# rf_board.net
KiCad netlist of a schematic drawn in EAGLE
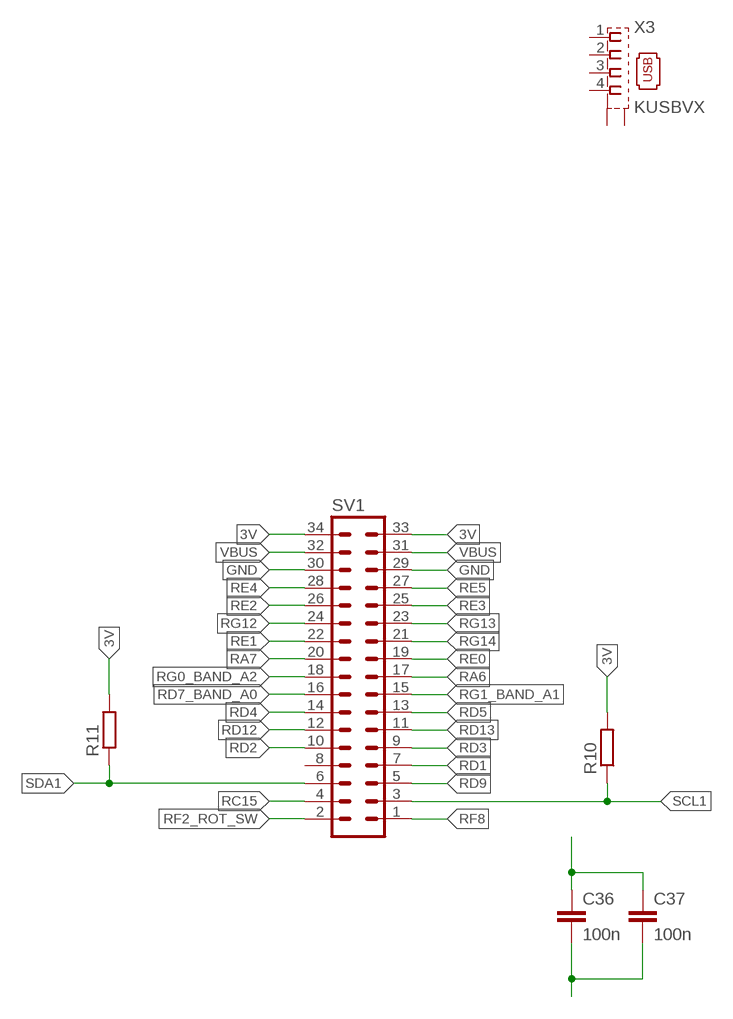
[diagram p0: schematic, sheet 1, part 1 of 2]
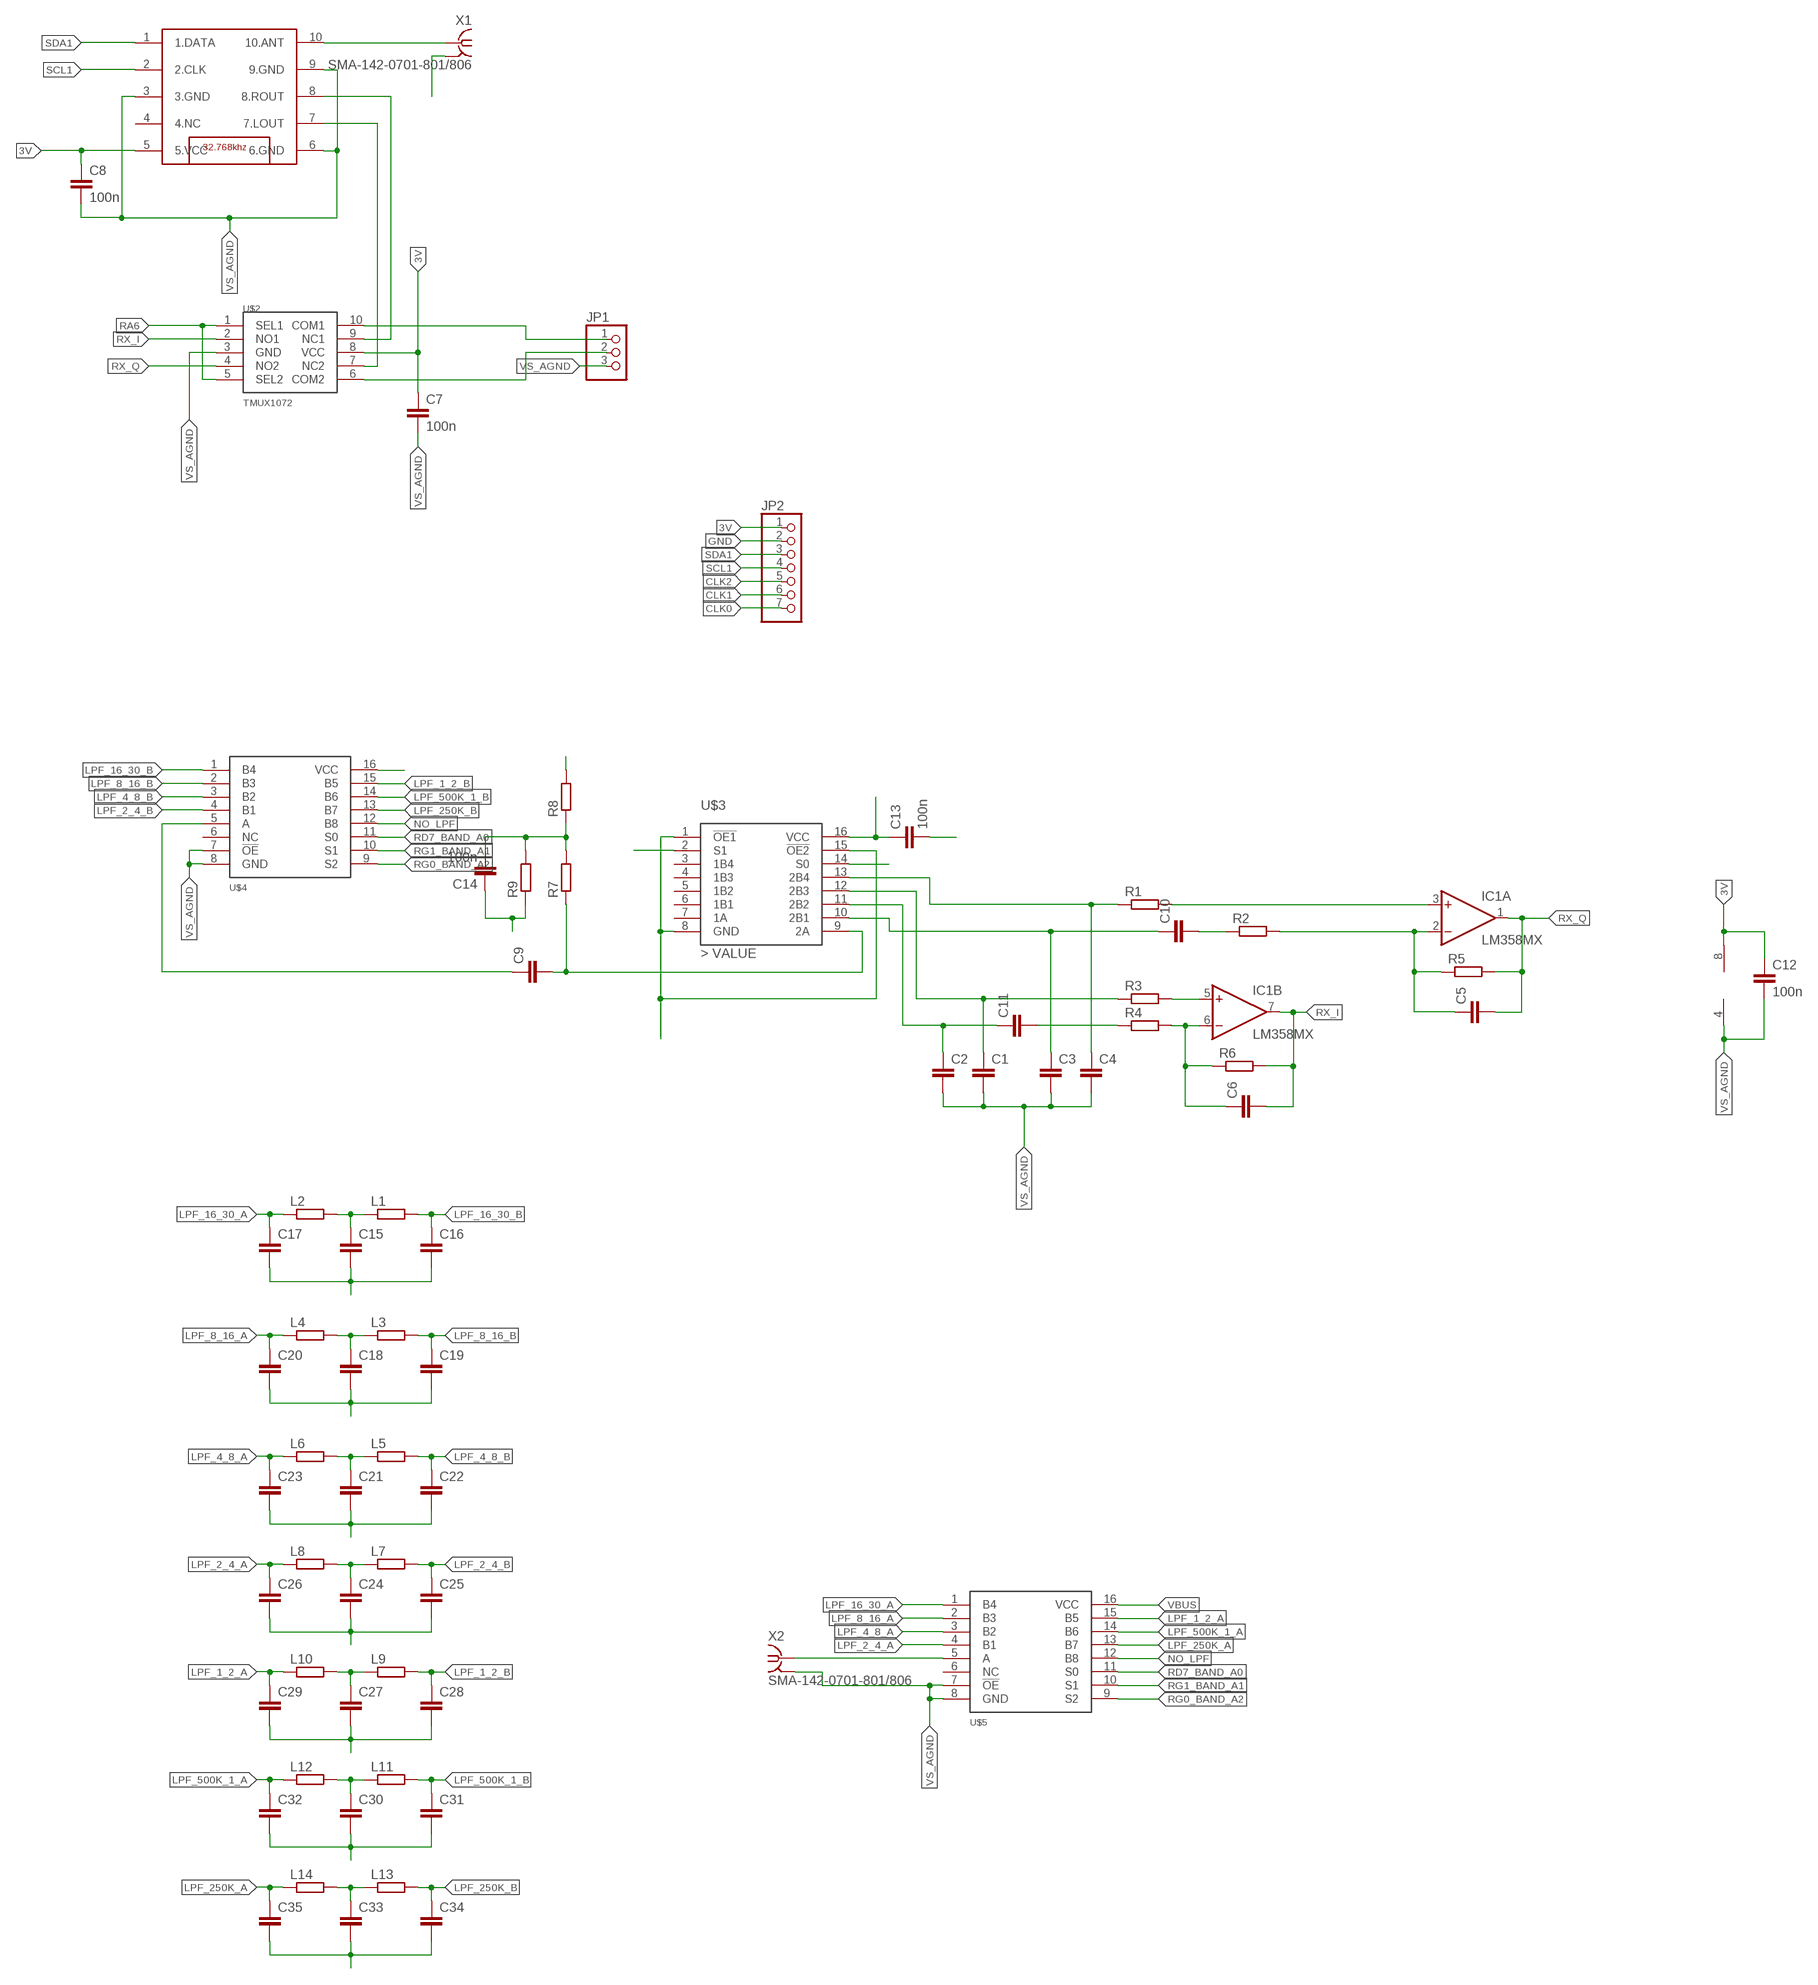
[diagram p1: schematic, sheet 1, part 2 of 2]

(export (version "E")
  (design (tool "Eeschema 10.0.6"))
  (components
    (comp (ref "C1")
      (value "C-EUC0603")
      (footprint "eagle-import:C0603")
      (libsource (lib "eagle-import") (part "C-EUC0603"))
    )
    (comp (ref "C2")
      (value "C-EUC0603")
      (footprint "eagle-import:C0603")
      (libsource (lib "eagle-import") (part "C-EUC0603"))
    )
    (comp (ref "C3")
      (value "C-EUC0603")
      (footprint "eagle-import:C0603")
      (libsource (lib "eagle-import") (part "C-EUC0603"))
    )
    (comp (ref "C4")
      (value "C-EUC0603")
      (footprint "eagle-import:C0603")
      (libsource (lib "eagle-import") (part "C-EUC0603"))
    )
    (comp (ref "C5")
      (value "C-EUC0603")
      (footprint "eagle-import:C0603")
      (libsource (lib "eagle-import") (part "C-EUC0603"))
    )
    (comp (ref "C6")
      (value "C-EUC0603")
      (footprint "eagle-import:C0603")
      (libsource (lib "eagle-import") (part "C-EUC0603"))
    )
    (comp (ref "C7")
      (value "100n")
      (footprint "eagle-import:C1206")
      (libsource (lib "eagle-import") (part "C-EUC1206"))
    )
    (comp (ref "C8")
      (value "100n")
      (footprint "eagle-import:C0603")
      (libsource (lib "eagle-import") (part "C-EUC0603"))
    )
    (comp (ref "C9")
      (value "C-EUC0603")
      (footprint "eagle-import:C0603")
      (libsource (lib "eagle-import") (part "C-EUC0603"))
    )
    (comp (ref "C10")
      (value "C-EUC0603")
      (footprint "eagle-import:C0603")
      (libsource (lib "eagle-import") (part "C-EUC0603"))
    )
    (comp (ref "C11")
      (value "C-EUC0603")
      (footprint "eagle-import:C0603")
      (libsource (lib "eagle-import") (part "C-EUC0603"))
    )
    (comp (ref "C12")
      (value "100n")
      (footprint "eagle-import:C0603")
      (libsource (lib "eagle-import") (part "C-EUC0603"))
    )
    (comp (ref "C13")
      (value "100n")
      (footprint "eagle-import:C0603")
      (libsource (lib "eagle-import") (part "C-EUC0603"))
    )
    (comp (ref "C14")
      (value "100n")
      (footprint "eagle-import:C0603")
      (libsource (lib "eagle-import") (part "C-EUC0603"))
    )
    (comp (ref "C15")
      (value "C-EUC0805")
      (footprint "eagle-import:C0805")
      (libsource (lib "eagle-import") (part "C-EUC0805"))
    )
    (comp (ref "C16")
      (value "C-EUC0805")
      (footprint "eagle-import:C0805")
      (libsource (lib "eagle-import") (part "C-EUC0805"))
    )
    (comp (ref "C17")
      (value "C-EUC0805")
      (footprint "eagle-import:C0805")
      (libsource (lib "eagle-import") (part "C-EUC0805"))
    )
    (comp (ref "C18")
      (value "C-EUC0805")
      (footprint "eagle-import:C0805")
      (libsource (lib "eagle-import") (part "C-EUC0805"))
    )
    (comp (ref "C19")
      (value "C-EUC0805")
      (footprint "eagle-import:C0805")
      (libsource (lib "eagle-import") (part "C-EUC0805"))
    )
    (comp (ref "C20")
      (value "C-EUC0805")
      (footprint "eagle-import:C0805")
      (libsource (lib "eagle-import") (part "C-EUC0805"))
    )
    (comp (ref "C21")
      (value "C-EUC0805")
      (footprint "eagle-import:C0805")
      (libsource (lib "eagle-import") (part "C-EUC0805"))
    )
    (comp (ref "C22")
      (value "C-EUC0805")
      (footprint "eagle-import:C0805")
      (libsource (lib "eagle-import") (part "C-EUC0805"))
    )
    (comp (ref "C23")
      (value "C-EUC0805")
      (footprint "eagle-import:C0805")
      (libsource (lib "eagle-import") (part "C-EUC0805"))
    )
    (comp (ref "C24")
      (value "C-EUC0805")
      (footprint "eagle-import:C0805")
      (libsource (lib "eagle-import") (part "C-EUC0805"))
    )
    (comp (ref "C25")
      (value "C-EUC0805")
      (footprint "eagle-import:C0805")
      (libsource (lib "eagle-import") (part "C-EUC0805"))
    )
    (comp (ref "C26")
      (value "C-EUC0805")
      (footprint "eagle-import:C0805")
      (libsource (lib "eagle-import") (part "C-EUC0805"))
    )
    (comp (ref "C27")
      (value "C-EUC0805")
      (footprint "eagle-import:C0805")
      (libsource (lib "eagle-import") (part "C-EUC0805"))
    )
    (comp (ref "C28")
      (value "C-EUC0805")
      (footprint "eagle-import:C0805")
      (libsource (lib "eagle-import") (part "C-EUC0805"))
    )
    (comp (ref "C29")
      (value "C-EUC0805")
      (footprint "eagle-import:C0805")
      (libsource (lib "eagle-import") (part "C-EUC0805"))
    )
    (comp (ref "C30")
      (value "C-EUC0805")
      (footprint "eagle-import:C0805")
      (libsource (lib "eagle-import") (part "C-EUC0805"))
    )
    (comp (ref "C31")
      (value "C-EUC0805")
      (footprint "eagle-import:C0805")
      (libsource (lib "eagle-import") (part "C-EUC0805"))
    )
    (comp (ref "C32")
      (value "C-EUC0805")
      (footprint "eagle-import:C0805")
      (libsource (lib "eagle-import") (part "C-EUC0805"))
    )
    (comp (ref "C33")
      (value "C-EUC0805")
      (footprint "eagle-import:C0805")
      (libsource (lib "eagle-import") (part "C-EUC0805"))
    )
    (comp (ref "C34")
      (value "C-EUC0805")
      (footprint "eagle-import:C0805")
      (libsource (lib "eagle-import") (part "C-EUC0805"))
    )
    (comp (ref "C35")
      (value "C-EUC0805")
      (footprint "eagle-import:C0805")
      (libsource (lib "eagle-import") (part "C-EUC0805"))
    )
    (comp (ref "C36")
      (value "100n")
      (footprint "eagle-import:C0603")
      (libsource (lib "eagle-import") (part "C-EUC0603"))
    )
    (comp (ref "C37")
      (value "100n")
      (footprint "eagle-import:C0603")
      (libsource (lib "eagle-import") (part "C-EUC0603"))
    )
    (comp (ref "IC1")
      (value "LM358MX")
      (footprint "eagle-import:SO08")
      (libsource (lib "eagle-import") (part "LM358MX"))
    )
    (comp (ref "JP1")
      (value "PINHD-1X3")
      (footprint "eagle-import:1X03")
      (libsource (lib "eagle-import") (part "PINHD-1X3"))
    )
    (comp (ref "JP2")
      (value "PINHD-1X7")
      (footprint "eagle-import:1X07")
      (libsource (lib "eagle-import") (part "PINHD-1X7"))
    )
    (comp (ref "L1")
      (value "R-EU_R0805")
      (footprint "eagle-import:R0805")
      (libsource (lib "eagle-import") (part "R-EU_R0805"))
    )
    (comp (ref "L2")
      (value "R-EU_R0805")
      (footprint "eagle-import:R0805")
      (libsource (lib "eagle-import") (part "R-EU_R0805"))
    )
    (comp (ref "L3")
      (value "R-EU_R0805")
      (footprint "eagle-import:R0805")
      (libsource (lib "eagle-import") (part "R-EU_R0805"))
    )
    (comp (ref "L4")
      (value "R-EU_R0805")
      (footprint "eagle-import:R0805")
      (libsource (lib "eagle-import") (part "R-EU_R0805"))
    )
    (comp (ref "L5")
      (value "R-EU_R0805")
      (footprint "eagle-import:R0805")
      (libsource (lib "eagle-import") (part "R-EU_R0805"))
    )
    (comp (ref "L6")
      (value "R-EU_R0805")
      (footprint "eagle-import:R0805")
      (libsource (lib "eagle-import") (part "R-EU_R0805"))
    )
    (comp (ref "L7")
      (value "R-EU_R0805")
      (footprint "eagle-import:R0805")
      (libsource (lib "eagle-import") (part "R-EU_R0805"))
    )
    (comp (ref "L8")
      (value "R-EU_R0805")
      (footprint "eagle-import:R0805")
      (libsource (lib "eagle-import") (part "R-EU_R0805"))
    )
    (comp (ref "L9")
      (value "R-EU_R0805")
      (footprint "eagle-import:R0805")
      (libsource (lib "eagle-import") (part "R-EU_R0805"))
    )
    (comp (ref "L10")
      (value "R-EU_R0805")
      (footprint "eagle-import:R0805")
      (libsource (lib "eagle-import") (part "R-EU_R0805"))
    )
    (comp (ref "L11")
      (value "R-EU_R0805")
      (footprint "eagle-import:R0805")
      (libsource (lib "eagle-import") (part "R-EU_R0805"))
    )
    (comp (ref "L12")
      (value "R-EU_R0805")
      (footprint "eagle-import:R0805")
      (libsource (lib "eagle-import") (part "R-EU_R0805"))
    )
    (comp (ref "L13")
      (value "R-EU_R0805")
      (footprint "eagle-import:R0805")
      (libsource (lib "eagle-import") (part "R-EU_R0805"))
    )
    (comp (ref "L14")
      (value "R-EU_R0805")
      (footprint "eagle-import:R0805")
      (libsource (lib "eagle-import") (part "R-EU_R0805"))
    )
    (comp (ref "R1")
      (value "R-EU_R0603")
      (footprint "eagle-import:R0603")
      (libsource (lib "eagle-import") (part "R-EU_R0603"))
    )
    (comp (ref "R2")
      (value "R-EU_R0603")
      (footprint "eagle-import:R0603")
      (libsource (lib "eagle-import") (part "R-EU_R0603"))
    )
    (comp (ref "R3")
      (value "R-EU_R0603")
      (footprint "eagle-import:R0603")
      (libsource (lib "eagle-import") (part "R-EU_R0603"))
    )
    (comp (ref "R4")
      (value "R-EU_R0603")
      (footprint "eagle-import:R0603")
      (libsource (lib "eagle-import") (part "R-EU_R0603"))
    )
    (comp (ref "R5")
      (value "R-EU_R0603")
      (footprint "eagle-import:R0603")
      (libsource (lib "eagle-import") (part "R-EU_R0603"))
    )
    (comp (ref "R6")
      (value "R-EU_R0603")
      (footprint "eagle-import:R0603")
      (libsource (lib "eagle-import") (part "R-EU_R0603"))
    )
    (comp (ref "R7")
      (value "R-EU_0204/5")
      (footprint "eagle-import:0204_5")
      (libsource (lib "eagle-import") (part "R-EU_0204/5"))
    )
    (comp (ref "R8")
      (value "R-EU_R0603")
      (footprint "eagle-import:R0603")
      (libsource (lib "eagle-import") (part "R-EU_R0603"))
    )
    (comp (ref "R9")
      (value "R-EU_R0603")
      (footprint "eagle-import:R0603")
      (libsource (lib "eagle-import") (part "R-EU_R0603"))
    )
    (comp (ref "R10")
      (value "R-EU_0204/7")
      (footprint "eagle-import:0204_7")
      (libsource (lib "eagle-import") (part "R-EU_0204/7"))
    )
    (comp (ref "R11")
      (value "R-EU_0204/5")
      (footprint "eagle-import:0204_5")
      (libsource (lib "eagle-import") (part "R-EU_0204/5"))
    )
    (comp (ref "SV1")
      (value "ML34L")
      (footprint "eagle-import:ML34L")
      (libsource (lib "eagle-import") (part "ML34L"))
    )
    (comp (ref "U$1")
      (value "TEA5767")
      (footprint "eagle-import:TJ-102BC")
      (libsource (lib "eagle-import") (part "TEA5767"))
    )
    (comp (ref "U$2")
      (value "TMUX1072")
      (footprint "eagle-import:TSSOP8")
      (libsource (lib "eagle-import") (part "TMUX1072"))
    )
    (comp (ref "U$3")
      (value "FST3253SO16")
      (footprint "eagle-import:SO16")
      (libsource (lib "eagle-import") (part "FST3253SO16"))
    )
    (comp (ref "U$4")
      (value "SN74CBT3251")
      (footprint "eagle-import:TSSOP16")
      (libsource (lib "eagle-import") (part "SN74CBT3251"))
    )
    (comp (ref "U$5")
      (value "SN74CBT3251")
      (footprint "eagle-import:TSSOP16")
      (libsource (lib "eagle-import") (part "SN74CBT3251"))
    )
    (comp (ref "X1")
      (value "SMA-142-0701-801/806")
      (footprint "eagle-import:J502-ND-142-0701-801_806")
      (fields (field (name "MF") "JOHNSON COMPONENTS") (field (name "MPN") "142-0701-801"))
      (libsource (lib "eagle-import") (part "SMA-142-0701-801/806"))
    )
    (comp (ref "X2")
      (value "SMA-142-0701-801/806")
      (footprint "eagle-import:J502-ND-142-0701-801_806")
      (fields (field (name "MF") "JOHNSON COMPONENTS") (field (name "MPN") "142-0701-801"))
      (libsource (lib "eagle-import") (part "SMA-142-0701-801/806"))
    )
    (comp (ref "X3")
      (value "KUSBVX")
      (footprint "eagle-import:KUSBVX")
      (libsource (lib "eagle-import") (part "KUSBVX"))
    )
  )
  (nets
    (net (code "1") (name "3V") (class "Default")
      (node (ref "C12") (pin "1") (pinfunction "1_1") (pintype "passive"))
      (node (ref "C13") (pin "1") (pinfunction "1_1") (pintype "passive"))
      (node (ref "C7") (pin "1") (pinfunction "1_1") (pintype "passive"))
      (node (ref "C8") (pin "1") (pinfunction "1_1") (pintype "passive"))
      (node (ref "IC1") (pin "8") (pinfunction "V+_8") (pintype "power_in"))
      (node (ref "JP2") (pin "1") (pinfunction "1_1") (pintype "passive"))
      (node (ref "R10") (pin "2") (pinfunction "2_2") (pintype "passive"))
      (node (ref "R11") (pin "2") (pinfunction "2_2") (pintype "passive"))
      (node (ref "R8") (pin "2") (pinfunction "2_2") (pintype "passive"))
      (node (ref "SV1") (pin "33") (pinfunction "33_33") (pintype "passive"))
      (node (ref "SV1") (pin "34") (pinfunction "34_34") (pintype "passive"))
      (node (ref "U$1") (pin "5") (pinfunction "5.VCC_5") (pintype "bidirectional"))
      (node (ref "U$2") (pin "8") (pinfunction "VCC_8") (pintype "bidirectional"))
      (node (ref "U$3") (pin "16") (pinfunction "VCC_16") (pintype "bidirectional"))
    )
    (net (code "2") (name "CLK0") (class "Default")
      (node (ref "JP2") (pin "7") (pinfunction "7_7") (pintype "passive"))
      (node (ref "U$3") (pin "14") (pinfunction "S0_14") (pintype "bidirectional"))
    )
    (net (code "3") (name "CLK1") (class "Default")
      (node (ref "JP2") (pin "6") (pinfunction "6_6") (pintype "passive"))
      (node (ref "U$3") (pin "2") (pinfunction "S1_2") (pintype "bidirectional"))
    )
    (net (code "4") (name "CLK2") (class "Default")
      (node (ref "JP2") (pin "5") (pinfunction "5_5") (pintype "passive"))
    )
    (net (code "5") (name "GND") (class "Default")
      (node (ref "JP2") (pin "2") (pinfunction "2_2") (pintype "passive"))
      (node (ref "SV1") (pin "29") (pinfunction "29_29") (pintype "passive"))
      (node (ref "SV1") (pin "30") (pinfunction "30_30") (pintype "passive"))
    )
    (net (code "6") (name "LPF_1_2_A") (class "Default")
      (node (ref "C29") (pin "1") (pinfunction "1_1") (pintype "passive"))
      (node (ref "L10") (pin "1") (pinfunction "1_1") (pintype "passive"))
      (node (ref "U$5") (pin "15") (pinfunction "B5_15") (pintype "bidirectional"))
    )
    (net (code "7") (name "LPF_1_2_B") (class "Default")
      (node (ref "C28") (pin "1") (pinfunction "1_1") (pintype "passive"))
      (node (ref "L9") (pin "2") (pinfunction "2_2") (pintype "passive"))
      (node (ref "U$4") (pin "15") (pinfunction "B5_15") (pintype "bidirectional"))
    )
    (net (code "8") (name "LPF_2_4_A") (class "Default")
      (node (ref "C26") (pin "1") (pinfunction "1_1") (pintype "passive"))
      (node (ref "L8") (pin "1") (pinfunction "1_1") (pintype "passive"))
      (node (ref "U$5") (pin "4") (pinfunction "B1_4") (pintype "bidirectional"))
    )
    (net (code "9") (name "LPF_2_4_B") (class "Default")
      (node (ref "C25") (pin "1") (pinfunction "1_1") (pintype "passive"))
      (node (ref "L7") (pin "2") (pinfunction "2_2") (pintype "passive"))
      (node (ref "U$4") (pin "4") (pinfunction "B1_4") (pintype "bidirectional"))
    )
    (net (code "10") (name "LPF_4_8_A") (class "Default")
      (node (ref "C23") (pin "1") (pinfunction "1_1") (pintype "passive"))
      (node (ref "L6") (pin "1") (pinfunction "1_1") (pintype "passive"))
      (node (ref "U$5") (pin "3") (pinfunction "B2_3") (pintype "bidirectional"))
    )
    (net (code "11") (name "LPF_4_8_B") (class "Default")
      (node (ref "C22") (pin "1") (pinfunction "1_1") (pintype "passive"))
      (node (ref "L5") (pin "2") (pinfunction "2_2") (pintype "passive"))
      (node (ref "U$4") (pin "3") (pinfunction "B2_3") (pintype "bidirectional"))
    )
    (net (code "12") (name "LPF_8_16_A") (class "Default")
      (node (ref "C20") (pin "1") (pinfunction "1_1") (pintype "passive"))
      (node (ref "L4") (pin "1") (pinfunction "1_1") (pintype "passive"))
      (node (ref "U$5") (pin "2") (pinfunction "B3_2") (pintype "bidirectional"))
    )
    (net (code "13") (name "LPF_8_16_B") (class "Default")
      (node (ref "C19") (pin "1") (pinfunction "1_1") (pintype "passive"))
      (node (ref "L3") (pin "2") (pinfunction "2_2") (pintype "passive"))
      (node (ref "U$4") (pin "2") (pinfunction "B3_2") (pintype "bidirectional"))
    )
    (net (code "14") (name "LPF_16_30_A") (class "Default")
      (node (ref "C17") (pin "1") (pinfunction "1_1") (pintype "passive"))
      (node (ref "L2") (pin "1") (pinfunction "1_1") (pintype "passive"))
      (node (ref "U$5") (pin "1") (pinfunction "B4_1") (pintype "bidirectional"))
    )
    (net (code "15") (name "LPF_16_30_B") (class "Default")
      (node (ref "C16") (pin "1") (pinfunction "1_1") (pintype "passive"))
      (node (ref "L1") (pin "2") (pinfunction "2_2") (pintype "passive"))
      (node (ref "U$4") (pin "1") (pinfunction "B4_1") (pintype "bidirectional"))
    )
    (net (code "16") (name "LPF_250K_A") (class "Default")
      (node (ref "C35") (pin "1") (pinfunction "1_1") (pintype "passive"))
      (node (ref "L14") (pin "1") (pinfunction "1_1") (pintype "passive"))
      (node (ref "U$5") (pin "13") (pinfunction "B7_13") (pintype "bidirectional"))
    )
    (net (code "17") (name "LPF_250K_B") (class "Default")
      (node (ref "C34") (pin "1") (pinfunction "1_1") (pintype "passive"))
      (node (ref "L13") (pin "2") (pinfunction "2_2") (pintype "passive"))
      (node (ref "U$4") (pin "13") (pinfunction "B7_13") (pintype "bidirectional"))
    )
    (net (code "18") (name "LPF_500K_1_A") (class "Default")
      (node (ref "C32") (pin "1") (pinfunction "1_1") (pintype "passive"))
      (node (ref "L12") (pin "1") (pinfunction "1_1") (pintype "passive"))
      (node (ref "U$5") (pin "14") (pinfunction "B6_14") (pintype "bidirectional"))
    )
    (net (code "19") (name "LPF_500K_1_B") (class "Default")
      (node (ref "C31") (pin "1") (pinfunction "1_1") (pintype "passive"))
      (node (ref "L11") (pin "2") (pinfunction "2_2") (pintype "passive"))
      (node (ref "U$4") (pin "14") (pinfunction "B6_14") (pintype "bidirectional"))
    )
    (net (code "20") (name "NO_LPF") (class "Default")
      (node (ref "U$4") (pin "12") (pinfunction "B8_12") (pintype "bidirectional"))
      (node (ref "U$5") (pin "12") (pinfunction "B8_12") (pintype "bidirectional"))
    )
    (net (code "21") (name "Net-(C10-Pad2)") (class "Default")
      (node (ref "C10") (pin "2") (pinfunction "2_2") (pintype "passive"))
      (node (ref "R2") (pin "1") (pinfunction "1_1") (pintype "passive"))
    )
    (net (code "22") (name "Net-(C11-Pad2)") (class "Default")
      (node (ref "C11") (pin "2") (pinfunction "2_2") (pintype "passive"))
      (node (ref "R4") (pin "1") (pinfunction "1_1") (pintype "passive"))
    )
    (net (code "23") (name "Net-(C14-Pad2)") (class "Default")
      (node (ref "C14") (pin "2") (pinfunction "2_2") (pintype "passive"))
      (node (ref "R7") (pin "2") (pinfunction "2_2") (pintype "passive"))
      (node (ref "R8") (pin "1") (pinfunction "1_1") (pintype "passive"))
      (node (ref "R9") (pin "2") (pinfunction "2_2") (pintype "passive"))
    )
    (net (code "24") (name "Net-(C15-Pad1)") (class "Default")
      (node (ref "C15") (pin "1") (pinfunction "1_1") (pintype "passive"))
      (node (ref "L1") (pin "1") (pinfunction "1_1") (pintype "passive"))
      (node (ref "L2") (pin "2") (pinfunction "2_2") (pintype "passive"))
    )
    (net (code "25") (name "Net-(C18-Pad1)") (class "Default")
      (node (ref "C18") (pin "1") (pinfunction "1_1") (pintype "passive"))
      (node (ref "L3") (pin "1") (pinfunction "1_1") (pintype "passive"))
      (node (ref "L4") (pin "2") (pinfunction "2_2") (pintype "passive"))
    )
    (net (code "26") (name "Net-(C21-Pad1)") (class "Default")
      (node (ref "C21") (pin "1") (pinfunction "1_1") (pintype "passive"))
      (node (ref "L5") (pin "1") (pinfunction "1_1") (pintype "passive"))
      (node (ref "L6") (pin "2") (pinfunction "2_2") (pintype "passive"))
    )
    (net (code "27") (name "Net-(C24-Pad1)") (class "Default")
      (node (ref "C24") (pin "1") (pinfunction "1_1") (pintype "passive"))
      (node (ref "L7") (pin "1") (pinfunction "1_1") (pintype "passive"))
      (node (ref "L8") (pin "2") (pinfunction "2_2") (pintype "passive"))
    )
    (net (code "28") (name "Net-(C27-Pad1)") (class "Default")
      (node (ref "C27") (pin "1") (pinfunction "1_1") (pintype "passive"))
      (node (ref "L10") (pin "2") (pinfunction "2_2") (pintype "passive"))
      (node (ref "L9") (pin "1") (pinfunction "1_1") (pintype "passive"))
    )
    (net (code "29") (name "Net-(C30-Pad1)") (class "Default")
      (node (ref "C30") (pin "1") (pinfunction "1_1") (pintype "passive"))
      (node (ref "L11") (pin "1") (pinfunction "1_1") (pintype "passive"))
      (node (ref "L12") (pin "2") (pinfunction "2_2") (pintype "passive"))
    )
    (net (code "30") (name "Net-(C33-Pad1)") (class "Default")
      (node (ref "C33") (pin "1") (pinfunction "1_1") (pintype "passive"))
      (node (ref "L13") (pin "1") (pinfunction "1_1") (pintype "passive"))
      (node (ref "L14") (pin "2") (pinfunction "2_2") (pintype "passive"))
    )
    (net (code "31") (name "Net-(IC1A-+IN)") (class "Default")
      (node (ref "IC1") (pin "3") (pinfunction "+IN_3") (pintype "input"))
      (node (ref "R1") (pin "2") (pinfunction "2_2") (pintype "passive"))
    )
    (net (code "32") (name "Net-(IC1A--IN)") (class "Default")
      (node (ref "C5") (pin "1") (pinfunction "1_1") (pintype "passive"))
      (node (ref "IC1") (pin "2") (pinfunction "-IN_2") (pintype "input"))
      (node (ref "R2") (pin "2") (pinfunction "2_2") (pintype "passive"))
      (node (ref "R5") (pin "1") (pinfunction "1_1") (pintype "passive"))
    )
    (net (code "33") (name "Net-(IC1B-+IN)") (class "Default")
      (node (ref "IC1") (pin "5") (pinfunction "+IN_5") (pintype "input"))
      (node (ref "R3") (pin "2") (pinfunction "2_2") (pintype "passive"))
    )
    (net (code "34") (name "Net-(IC1B--IN)") (class "Default")
      (node (ref "C6") (pin "1") (pinfunction "1_1") (pintype "passive"))
      (node (ref "IC1") (pin "6") (pinfunction "-IN_6") (pintype "input"))
      (node (ref "R4") (pin "2") (pinfunction "2_2") (pintype "passive"))
      (node (ref "R6") (pin "1") (pinfunction "1_1") (pintype "passive"))
    )
    (net (code "35") (name "Net-(U$1-7.LOUT)") (class "Default")
      (node (ref "U$1") (pin "7") (pinfunction "7.LOUT_7") (pintype "bidirectional"))
      (node (ref "U$2") (pin "7") (pinfunction "NC2_7") (pintype "bidirectional"))
    )
    (net (code "36") (name "Net-(U$1-8.ROUT)") (class "Default")
      (node (ref "U$1") (pin "8") (pinfunction "8.ROUT_8") (pintype "bidirectional"))
      (node (ref "U$2") (pin "9") (pinfunction "NC1_9") (pintype "bidirectional"))
    )
    (net (code "37") (name "Net-(U$1-10.ANT)") (class "Default")
      (node (ref "U$1") (pin "10") (pinfunction "10.ANT_10") (pintype "bidirectional"))
      (node (ref "X1") (pin "1") (pinfunction "1_1") (pintype "passive"))
    )
    (net (code "38") (name "Net-(U$2-COM1)") (class "Default")
      (node (ref "JP1") (pin "1") (pinfunction "1_1") (pintype "passive"))
      (node (ref "U$2") (pin "10") (pinfunction "COM1_10") (pintype "bidirectional"))
    )
    (net (code "39") (name "Net-(U$2-COM2)") (class "Default")
      (node (ref "JP1") (pin "2") (pinfunction "2_2") (pintype "passive"))
      (node (ref "U$2") (pin "6") (pinfunction "COM2_6") (pintype "bidirectional"))
    )
    (net (code "40") (name "Net-(U$3-2A)") (class "Default")
      (node (ref "C9") (pin "2") (pinfunction "2_2") (pintype "passive"))
      (node (ref "R7") (pin "1") (pinfunction "1_1") (pintype "passive"))
      (node (ref "U$3") (pin "9") (pinfunction "2A_9") (pintype "bidirectional"))
    )
    (net (code "41") (name "Net-(U$3-2B1)") (class "Default")
      (node (ref "C10") (pin "1") (pinfunction "1_1") (pintype "passive"))
      (node (ref "C3") (pin "1") (pinfunction "1_1") (pintype "passive"))
      (node (ref "U$3") (pin "10") (pinfunction "2B1_10") (pintype "bidirectional"))
    )
    (net (code "42") (name "Net-(U$3-2B2)") (class "Default")
      (node (ref "C11") (pin "1") (pinfunction "1_1") (pintype "passive"))
      (node (ref "C2") (pin "1") (pinfunction "1_1") (pintype "passive"))
      (node (ref "U$3") (pin "11") (pinfunction "2B2_11") (pintype "bidirectional"))
    )
    (net (code "43") (name "Net-(U$3-2B3)") (class "Default")
      (node (ref "C1") (pin "1") (pinfunction "1_1") (pintype "passive"))
      (node (ref "R3") (pin "1") (pinfunction "1_1") (pintype "passive"))
      (node (ref "U$3") (pin "12") (pinfunction "2B3_12") (pintype "bidirectional"))
    )
    (net (code "44") (name "Net-(U$3-2B4)") (class "Default")
      (node (ref "C4") (pin "1") (pinfunction "1_1") (pintype "passive"))
      (node (ref "R1") (pin "1") (pinfunction "1_1") (pintype "passive"))
      (node (ref "U$3") (pin "13") (pinfunction "2B4_13") (pintype "bidirectional"))
    )
    (net (code "45") (name "Net-(U$4-A)") (class "Default")
      (node (ref "C9") (pin "1") (pinfunction "1_1") (pintype "passive"))
      (node (ref "U$4") (pin "5") (pinfunction "A_5") (pintype "bidirectional"))
    )
    (net (code "46") (name "Net-(U$5-A)") (class "Default")
      (node (ref "U$5") (pin "5") (pinfunction "A_5") (pintype "bidirectional"))
      (node (ref "X2") (pin "1") (pinfunction "1_1") (pintype "passive"))
    )
    (net (code "47") (name "RA6") (class "Default")
      (node (ref "SV1") (pin "17") (pinfunction "17_17") (pintype "passive"))
      (node (ref "U$2") (pin "1") (pinfunction "SEL1_1") (pintype "bidirectional"))
      (node (ref "U$2") (pin "5") (pinfunction "SEL2_5") (pintype "bidirectional"))
    )
    (net (code "48") (name "RA7") (class "Default")
      (node (ref "SV1") (pin "20") (pinfunction "20_20") (pintype "passive"))
    )
    (net (code "49") (name "RC15") (class "Default")
      (node (ref "SV1") (pin "4") (pinfunction "4_4") (pintype "passive"))
    )
    (net (code "50") (name "RD1") (class "Default")
      (node (ref "SV1") (pin "7") (pinfunction "7_7") (pintype "passive"))
    )
    (net (code "51") (name "RD2") (class "Default")
      (node (ref "SV1") (pin "10") (pinfunction "10_10") (pintype "passive"))
    )
    (net (code "52") (name "RD3") (class "Default")
      (node (ref "SV1") (pin "9") (pinfunction "9_9") (pintype "passive"))
    )
    (net (code "53") (name "RD4") (class "Default")
      (node (ref "SV1") (pin "14") (pinfunction "14_14") (pintype "passive"))
    )
    (net (code "54") (name "RD5") (class "Default")
      (node (ref "SV1") (pin "13") (pinfunction "13_13") (pintype "passive"))
    )
    (net (code "55") (name "RD7_BAND_A0") (class "Default")
      (node (ref "SV1") (pin "16") (pinfunction "16_16") (pintype "passive"))
      (node (ref "U$4") (pin "11") (pinfunction "S0_11") (pintype "bidirectional"))
      (node (ref "U$5") (pin "11") (pinfunction "S0_11") (pintype "bidirectional"))
    )
    (net (code "56") (name "RD9") (class "Default")
      (node (ref "SV1") (pin "5") (pinfunction "5_5") (pintype "passive"))
    )
    (net (code "57") (name "RD12") (class "Default")
      (node (ref "SV1") (pin "12") (pinfunction "12_12") (pintype "passive"))
    )
    (net (code "58") (name "RD13") (class "Default")
      (node (ref "SV1") (pin "11") (pinfunction "11_11") (pintype "passive"))
    )
    (net (code "59") (name "RE0") (class "Default")
      (node (ref "SV1") (pin "19") (pinfunction "19_19") (pintype "passive"))
    )
    (net (code "60") (name "RE1") (class "Default")
      (node (ref "SV1") (pin "22") (pinfunction "22_22") (pintype "passive"))
    )
    (net (code "61") (name "RE2") (class "Default")
      (node (ref "SV1") (pin "26") (pinfunction "26_26") (pintype "passive"))
    )
    (net (code "62") (name "RE3") (class "Default")
      (node (ref "SV1") (pin "25") (pinfunction "25_25") (pintype "passive"))
    )
    (net (code "63") (name "RE4") (class "Default")
      (node (ref "SV1") (pin "28") (pinfunction "28_28") (pintype "passive"))
    )
    (net (code "64") (name "RE5") (class "Default")
      (node (ref "SV1") (pin "27") (pinfunction "27_27") (pintype "passive"))
    )
    (net (code "65") (name "RF2_ROT_SW") (class "Default")
      (node (ref "SV1") (pin "2") (pinfunction "2_2") (pintype "passive"))
    )
    (net (code "66") (name "RF8") (class "Default")
      (node (ref "SV1") (pin "1") (pinfunction "1_1") (pintype "passive"))
    )
    (net (code "67") (name "RG0_BAND_A2") (class "Default")
      (node (ref "SV1") (pin "18") (pinfunction "18_18") (pintype "passive"))
      (node (ref "U$4") (pin "9") (pinfunction "S2_9") (pintype "bidirectional"))
      (node (ref "U$5") (pin "9") (pinfunction "S2_9") (pintype "bidirectional"))
    )
    (net (code "68") (name "RG1_BAND_A1") (class "Default")
      (node (ref "SV1") (pin "15") (pinfunction "15_15") (pintype "passive"))
      (node (ref "U$4") (pin "10") (pinfunction "S1_10") (pintype "bidirectional"))
      (node (ref "U$5") (pin "10") (pinfunction "S1_10") (pintype "bidirectional"))
    )
    (net (code "69") (name "RG12") (class "Default")
      (node (ref "SV1") (pin "24") (pinfunction "24_24") (pintype "passive"))
    )
    (net (code "70") (name "RG13") (class "Default")
      (node (ref "SV1") (pin "23") (pinfunction "23_23") (pintype "passive"))
    )
    (net (code "71") (name "RG14") (class "Default")
      (node (ref "SV1") (pin "21") (pinfunction "21_21") (pintype "passive"))
    )
    (net (code "72") (name "RX_I") (class "Default")
      (node (ref "C6") (pin "2") (pinfunction "2_2") (pintype "passive"))
      (node (ref "IC1") (pin "7") (pinfunction "OUT_7") (pintype "output"))
      (node (ref "R6") (pin "2") (pinfunction "2_2") (pintype "passive"))
      (node (ref "U$2") (pin "2") (pinfunction "NO1_2") (pintype "bidirectional"))
    )
    (net (code "73") (name "RX_Q") (class "Default")
      (node (ref "C5") (pin "2") (pinfunction "2_2") (pintype "passive"))
      (node (ref "IC1") (pin "1") (pinfunction "OUT_1") (pintype "output"))
      (node (ref "R5") (pin "2") (pinfunction "2_2") (pintype "passive"))
      (node (ref "U$2") (pin "4") (pinfunction "NO2_4") (pintype "bidirectional"))
    )
    (net (code "74") (name "SCL1") (class "Default")
      (node (ref "JP2") (pin "4") (pinfunction "4_4") (pintype "passive"))
      (node (ref "R10") (pin "1") (pinfunction "1_1") (pintype "passive"))
      (node (ref "SV1") (pin "3") (pinfunction "3_3") (pintype "passive"))
      (node (ref "U$1") (pin "2") (pinfunction "2.CLK_2") (pintype "bidirectional"))
    )
    (net (code "75") (name "SDA1") (class "Default")
      (node (ref "JP2") (pin "3") (pinfunction "3_3") (pintype "passive"))
      (node (ref "R11") (pin "1") (pinfunction "1_1") (pintype "passive"))
      (node (ref "SV1") (pin "6") (pinfunction "6_6") (pintype "passive"))
      (node (ref "U$1") (pin "1") (pinfunction "1.DATA_1") (pintype "bidirectional"))
    )
    (net (code "76") (name "VBUS") (class "Default")
      (node (ref "C36") (pin "1") (pinfunction "1_1") (pintype "passive"))
      (node (ref "C37") (pin "1") (pinfunction "1_1") (pintype "passive"))
      (node (ref "SV1") (pin "31") (pinfunction "31_31") (pintype "passive"))
      (node (ref "SV1") (pin "32") (pinfunction "32_32") (pintype "passive"))
      (node (ref "U$4") (pin "16") (pinfunction "VCC_16") (pintype "bidirectional"))
      (node (ref "U$5") (pin "16") (pinfunction "VCC_16") (pintype "bidirectional"))
    )
    (net (code "77") (name "VS_AGND") (class "Default")
      (node (ref "C1") (pin "2") (pinfunction "2_2") (pintype "passive"))
      (node (ref "C12") (pin "2") (pinfunction "2_2") (pintype "passive"))
      (node (ref "C13") (pin "2") (pinfunction "2_2") (pintype "passive"))
      (node (ref "C14") (pin "1") (pinfunction "1_1") (pintype "passive"))
      (node (ref "C15") (pin "2") (pinfunction "2_2") (pintype "passive"))
      (node (ref "C16") (pin "2") (pinfunction "2_2") (pintype "passive"))
      (node (ref "C17") (pin "2") (pinfunction "2_2") (pintype "passive"))
      (node (ref "C18") (pin "2") (pinfunction "2_2") (pintype "passive"))
      (node (ref "C19") (pin "2") (pinfunction "2_2") (pintype "passive"))
      (node (ref "C2") (pin "2") (pinfunction "2_2") (pintype "passive"))
      (node (ref "C20") (pin "2") (pinfunction "2_2") (pintype "passive"))
      (node (ref "C21") (pin "2") (pinfunction "2_2") (pintype "passive"))
      (node (ref "C22") (pin "2") (pinfunction "2_2") (pintype "passive"))
      (node (ref "C23") (pin "2") (pinfunction "2_2") (pintype "passive"))
      (node (ref "C24") (pin "2") (pinfunction "2_2") (pintype "passive"))
      (node (ref "C25") (pin "2") (pinfunction "2_2") (pintype "passive"))
      (node (ref "C26") (pin "2") (pinfunction "2_2") (pintype "passive"))
      (node (ref "C27") (pin "2") (pinfunction "2_2") (pintype "passive"))
      (node (ref "C28") (pin "2") (pinfunction "2_2") (pintype "passive"))
      (node (ref "C29") (pin "2") (pinfunction "2_2") (pintype "passive"))
      (node (ref "C3") (pin "2") (pinfunction "2_2") (pintype "passive"))
      (node (ref "C30") (pin "2") (pinfunction "2_2") (pintype "passive"))
      (node (ref "C31") (pin "2") (pinfunction "2_2") (pintype "passive"))
      (node (ref "C32") (pin "2") (pinfunction "2_2") (pintype "passive"))
      (node (ref "C33") (pin "2") (pinfunction "2_2") (pintype "passive"))
      (node (ref "C34") (pin "2") (pinfunction "2_2") (pintype "passive"))
      (node (ref "C35") (pin "2") (pinfunction "2_2") (pintype "passive"))
      (node (ref "C36") (pin "2") (pinfunction "2_2") (pintype "passive"))
      (node (ref "C37") (pin "2") (pinfunction "2_2") (pintype "passive"))
      (node (ref "C4") (pin "2") (pinfunction "2_2") (pintype "passive"))
      (node (ref "C7") (pin "2") (pinfunction "2_2") (pintype "passive"))
      (node (ref "C8") (pin "2") (pinfunction "2_2") (pintype "passive"))
      (node (ref "IC1") (pin "4") (pinfunction "V-_4") (pintype "power_in"))
      (node (ref "JP1") (pin "3") (pinfunction "3_3") (pintype "passive"))
      (node (ref "R9") (pin "1") (pinfunction "1_1") (pintype "passive"))
      (node (ref "U$1") (pin "3") (pinfunction "3.GND_3") (pintype "bidirectional"))
      (node (ref "U$1") (pin "6") (pinfunction "6.GND_6") (pintype "bidirectional"))
      (node (ref "U$1") (pin "9") (pinfunction "9.GND_9") (pintype "bidirectional"))
      (node (ref "U$2") (pin "3") (pinfunction "GND_3") (pintype "bidirectional"))
      (node (ref "U$3") (pin "1") (pinfunction "~{OE1}_1") (pintype "bidirectional"))
      (node (ref "U$3") (pin "15") (pinfunction "~{OE2}_15") (pintype "bidirectional"))
      (node (ref "U$3") (pin "8") (pinfunction "GND_8") (pintype "bidirectional"))
      (node (ref "U$4") (pin "7") (pinfunction "~{OE}_7") (pintype "bidirectional"))
      (node (ref "U$4") (pin "8") (pinfunction "GND_8") (pintype "bidirectional"))
      (node (ref "U$5") (pin "7") (pinfunction "~{OE}_7") (pintype "bidirectional"))
      (node (ref "U$5") (pin "8") (pinfunction "GND_8") (pintype "bidirectional"))
      (node (ref "X1") (pin "G@1") (pinfunction "2_G@1") (pintype "passive"))
      (node (ref "X1") (pin "G@2") (pinfunction "2_G@2") (pintype "passive"))
      (node (ref "X1") (pin "G@3") (pinfunction "2_G@3") (pintype "passive"))
      (node (ref "X1") (pin "G@4") (pinfunction "2_G@4") (pintype "passive"))
      (node (ref "X2") (pin "G@1") (pinfunction "2_G@1") (pintype "passive"))
      (node (ref "X2") (pin "G@2") (pinfunction "2_G@2") (pintype "passive"))
      (node (ref "X2") (pin "G@3") (pinfunction "2_G@3") (pintype "passive"))
      (node (ref "X2") (pin "G@4") (pinfunction "2_G@4") (pintype "passive"))
    )
    (net (code "78") (name "unconnected-(SV1-Pad8)") (class "Default")
      (node (ref "SV1") (pin "8") (pinfunction "8_8") (pintype "passive"))
    )
    (net (code "79") (name "unconnected-(U$1-4.NC-Pad4)") (class "Default")
      (node (ref "U$1") (pin "4") (pinfunction "4.NC_4") (pintype "bidirectional"))
    )
    (net (code "80") (name "unconnected-(U$3-1A-Pad7)") (class "Default")
      (node (ref "U$3") (pin "7") (pinfunction "1A_7") (pintype "bidirectional"))
    )
    (net (code "81") (name "unconnected-(U$3-1B1-Pad6)") (class "Default")
      (node (ref "U$3") (pin "6") (pinfunction "1B1_6") (pintype "bidirectional"))
    )
    (net (code "82") (name "unconnected-(U$3-1B2-Pad5)") (class "Default")
      (node (ref "U$3") (pin "5") (pinfunction "1B2_5") (pintype "bidirectional"))
    )
    (net (code "83") (name "unconnected-(U$3-1B3-Pad4)") (class "Default")
      (node (ref "U$3") (pin "4") (pinfunction "1B3_4") (pintype "bidirectional"))
    )
    (net (code "84") (name "unconnected-(U$3-1B4-Pad3)") (class "Default")
      (node (ref "U$3") (pin "3") (pinfunction "1B4_3") (pintype "bidirectional"))
    )
    (net (code "85") (name "unconnected-(U$4-NC-Pad6)") (class "Default")
      (node (ref "U$4") (pin "6") (pinfunction "NC_6") (pintype "bidirectional"))
    )
    (net (code "86") (name "unconnected-(U$5-NC-Pad6)") (class "Default")
      (node (ref "U$5") (pin "6") (pinfunction "NC_6") (pintype "bidirectional"))
    )
    (net (code "87") (name "unconnected-(X3-Pad1)") (class "Default")
      (node (ref "X3") (pin "1") (pinfunction "1_1") (pintype "passive"))
    )
    (net (code "88") (name "unconnected-(X3-Pad2)") (class "Default")
      (node (ref "X3") (pin "2") (pinfunction "2_2") (pintype "passive"))
    )
    (net (code "89") (name "unconnected-(X3-Pad3)") (class "Default")
      (node (ref "X3") (pin "3") (pinfunction "3_3") (pintype "passive"))
    )
    (net (code "90") (name "unconnected-(X3-Pad4)") (class "Default")
      (node (ref "X3") (pin "4") (pinfunction "4_4") (pintype "passive"))
    )
    (net (code "91") (name "unconnected-(X3-S1-PadM1)") (class "Default")
      (node (ref "X3") (pin "M1") (pinfunction "S1_M1") (pintype "passive"))
    )
    (net (code "92") (name "unconnected-(X3-S2-PadM2)") (class "Default")
      (node (ref "X3") (pin "M2") (pinfunction "S2_M2") (pintype "passive"))
    )
  )
)
